# Microcontroller.net
KiCad netlist of a schematic drawn in Altium Designer
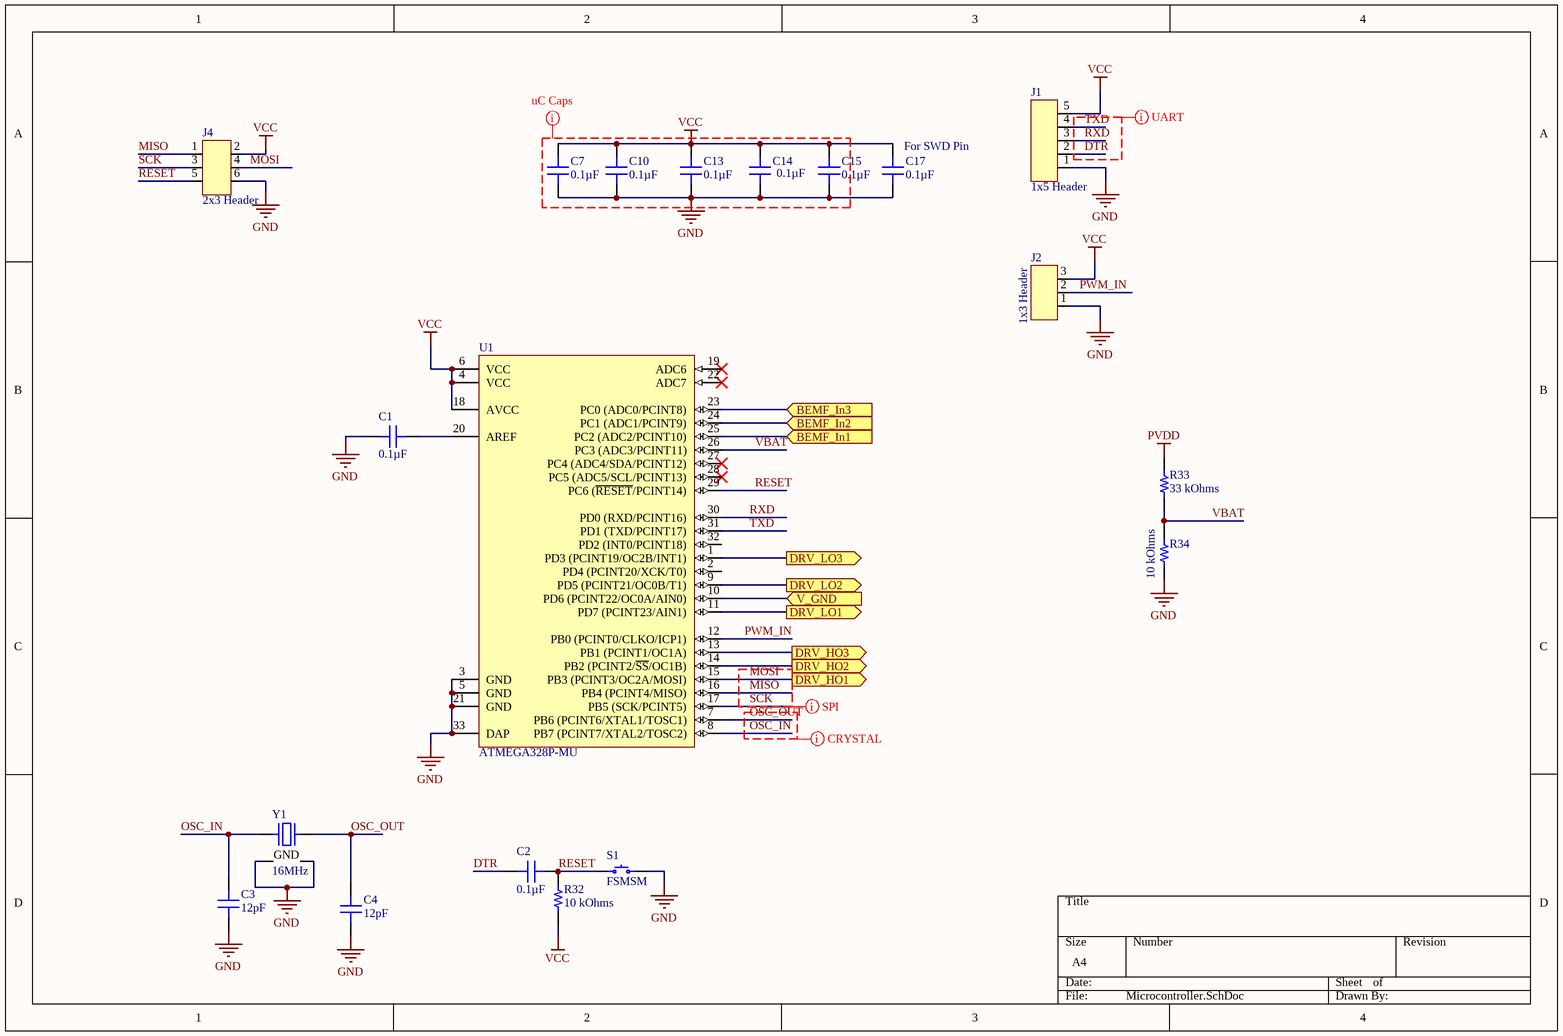
[diagram p0: Microcontroller.SchDoc]

(export (version "E")
  (design (tool "Eeschema 10.0.6"))
  (components
    (comp (ref "C1")
      (value "0.1µF")
      (footprint "CAP 0603_1608")
      (description "CAP CER 0.1UF 50V X7R 0603")
      (fields
        (field (name "PART NUMBER") "CML0603X7R104KT50V")
        (field (name "MANUFACTURER") "Stackpole Electronics Inc")
      )
      (libsource (lib "Celestial Altium Library - altium_library") (part "Capacitor"))
    )
    (comp (ref "C2")
      (value "0.1µF")
      (footprint "CAP 0603_1608")
      (description "CAP CER 0.1UF 50V X7R 0603")
      (fields
        (field (name "PART NUMBER") "CML0603X7R104KT50V")
        (field (name "MANUFACTURER") "Stackpole Electronics Inc")
      )
      (libsource (lib "Celestial Altium Library - altium_library") (part "Capacitor"))
    )
    (comp (ref "C3")
      (value "12pF")
      (footprint "CAP 0402_1005")
      (description "CAP CER 12PF 50V NP0 0402")
      (fields (field (name "PART NUMBER") "04025U120GAT2A") (field (name "MANUFACTURER") "AVX Corporation"))
      (libsource (lib "Celestial Altium Library - altium_library") (part "Capacitor"))
    )
    (comp (ref "C4")
      (value "12pF")
      (footprint "CAP 0402_1005")
      (description "CAP CER 12PF 50V NP0 0402")
      (fields (field (name "PART NUMBER") "04025U120GAT2A") (field (name "MANUFACTURER") "AVX Corporation"))
      (libsource (lib "Celestial Altium Library - altium_library") (part "Capacitor"))
    )
    (comp (ref "C7")
      (value "0.1µF")
      (footprint "CAP 0603_1608")
      (description "CAP CER 0.1UF 50V X7R 0603")
      (fields
        (field (name "PART NUMBER") "CML0603X7R104KT50V")
        (field (name "MANUFACTURER") "Stackpole Electronics Inc")
      )
      (libsource (lib "Celestial Altium Library - altium_library") (part "Capacitor"))
    )
    (comp (ref "C10")
      (value "0.1µF")
      (footprint "CAP 0603_1608")
      (description "CAP CER 0.1UF 50V X7R 0603")
      (fields
        (field (name "PART NUMBER") "CML0603X7R104KT50V")
        (field (name "MANUFACTURER") "Stackpole Electronics Inc")
      )
      (libsource (lib "Celestial Altium Library - altium_library") (part "Capacitor"))
    )
    (comp (ref "C13")
      (value "0.1µF")
      (footprint "CAP 0603_1608")
      (description "CAP CER 0.1UF 50V X7R 0603")
      (fields
        (field (name "PART NUMBER") "CML0603X7R104KT50V")
        (field (name "MANUFACTURER") "Stackpole Electronics Inc")
      )
      (libsource (lib "Celestial Altium Library - altium_library") (part "Capacitor"))
    )
    (comp (ref "C14")
      (value "0.1µF")
      (footprint "CAP 0603_1608")
      (description "CAP CER 0.1UF 50V X7R 0603")
      (fields
        (field (name "PART NUMBER") "CML0603X7R104KT50V")
        (field (name "MANUFACTURER") "Stackpole Electronics Inc")
      )
      (libsource (lib "Celestial Altium Library - altium_library") (part "Capacitor"))
    )
    (comp (ref "C15")
      (value "0.1µF")
      (footprint "CAP 0603_1608")
      (description "CAP CER 0.1UF 50V X7R 0603")
      (fields
        (field (name "PART NUMBER") "CML0603X7R104KT50V")
        (field (name "MANUFACTURER") "Stackpole Electronics Inc")
      )
      (libsource (lib "Celestial Altium Library - altium_library") (part "Capacitor"))
    )
    (comp (ref "C17")
      (value "0.1µF")
      (footprint "CAP 0603_1608")
      (description "CAP CER 0.1UF 50V X7R 0603")
      (fields
        (field (name "PART NUMBER") "CML0603X7R104KT50V")
        (field (name "MANUFACTURER") "Stackpole Electronics Inc")
      )
      (libsource (lib "Celestial Altium Library - altium_library") (part "Capacitor"))
    )
    (comp (ref "J1")
      (value "1x5 Header")
      (footprint "1X5-HEADER")
      (description "1X5 Male Header 2.54mm")
      (libsource (lib "UserIntegrated") (part "1x5 Header"))
    )
    (comp (ref "J2")
      (value "1x3 Header")
      (footprint "1x3Header")
      (description "1x3 Male Header 2.54mm")
      (libsource (lib "UserIntegrated") (part "1x3 Header"))
    )
    (comp (ref "J4")
      (value "2x3 Header")
      (footprint "3x2 Header")
      (description "2x3 Male Header 2.54mm")
      (libsource (lib "UserIntegrated") (part "2x3 Header"))
    )
    (comp (ref "R32")
      (value "10 kOhms")
      (footprint "RES 0805_2012")
      (description "RESTHINFILM 0805 10K0 0.1% 125MW")
      (fields (field (name "PART NUMBER") "CRT0805-BY-1002EST") (field (name "MANUFACTURER") "Bourns Inc."))
      (libsource (lib "Celestial Altium Library - altium_library") (part "Resistor"))
    )
    (comp (ref "R33")
      (value "33 kOhms")
      (footprint "RES 0805_2012")
      (description "RES SMD 33K OHM 1% 1/8W 0805")
      (fields (field (name "PART NUMBER") "CR0805-FX-3302ELF") (field (name "MANUFACTURER") "Bourns Inc."))
      (libsource (lib "Celestial Altium Library - altium_library") (part "Resistor"))
    )
    (comp (ref "R34")
      (value "10 kOhms")
      (footprint "RES 0805_2012")
      (description "RES 10K OHM 1% 1/8W 0805")
      (fields
        (field (name "PART NUMBER") "RN73R2ATTD1002F25")
        (field (name "MANUFACTURER") "KOA Speer Electronics, Inc.")
      )
      (libsource (lib "Celestial Altium Library - altium_library") (part "Resistor"))
    )
    (comp (ref "S1")
      (value "FSMSM")
      (footprint "TE FSMSMTR")
      (description "SWITCH TACTILE SPST-NO 0.05A 24V")
      (fields (field (name "MANUFACTURER") "TE Connectivity ALCOSWITCH Switches"))
      (libsource (lib "Celestial Altium Library - altium_library") (part "SPST-NO 2 PIN"))
    )
    (comp (ref "U1")
      (value "ATMEGA328P-MU")
      (footprint "QFN50P500X500X100_HS-33N")
      (libsource (lib "UserIntegrated") (part "ATMEGA328P-MU"))
    )
    (comp (ref "Y1")
      (value "16MHz")
      (footprint "NDK NX2520SA")
      (description "CRYSTAL 16MHZ 8PF SMD")
      (fields
        (field (name "PART NUMBER") "NX2520SA-16MHZ-EXS00A-CS11340")
        (field (name "MANUFACTURER") "NDK America, Inc.")
      )
      (libsource (lib "Celestial Altium Library - altium_library") (part "NDK Crystal NX2520SA"))
    )
  )
  (nets
    (net (code "1") (name "/BEMF_In1") (class "Default")
      (node (ref "U1") (pin "25") (pinfunction "PC2_(ADC2/PCINT10)_25") (pintype "bidirectional"))
    )
    (net (code "2") (name "/BEMF_In2") (class "Default")
      (node (ref "U1") (pin "24") (pinfunction "PC1_(ADC1/PCINT9)_24") (pintype "bidirectional"))
    )
    (net (code "3") (name "/BEMF_In3") (class "Default")
      (node (ref "U1") (pin "23") (pinfunction "PC0_(ADC0/PCINT8)_23") (pintype "bidirectional"))
    )
    (net (code "4") (name "/DRV_HO2") (class "Default")
      (node (ref "U1") (pin "14") (pinfunction "PB2_(PCINT2/~{SS}/OC1B)_14") (pintype "bidirectional"))
    )
    (net (code "5") (name "/DRV_HO3") (class "Default")
      (node (ref "U1") (pin "13") (pinfunction "PB1_(PCINT1/OC1A)_13") (pintype "bidirectional"))
    )
    (net (code "6") (name "/DRV_LO1") (class "Default")
      (node (ref "U1") (pin "11") (pinfunction "PD7_(PCINT23/AIN1)_11") (pintype "bidirectional"))
    )
    (net (code "7") (name "/DRV_LO2") (class "Default")
      (node (ref "U1") (pin "9") (pinfunction "PD5_(PCINT21/OC0B/T1)_9") (pintype "bidirectional"))
    )
    (net (code "8") (name "/DRV_LO3") (class "Default")
      (node (ref "U1") (pin "1") (pinfunction "PD3_(PCINT19/OC2B/INT1)_1") (pintype "bidirectional"))
    )
    (net (code "9") (name "/DTR") (class "Default")
      (node (ref "C2") (pin "2") (pinfunction "2_2") (pintype "passive"))
      (node (ref "J1") (pin "2") (pintype "passive"))
    )
    (net (code "10") (name "/MISO") (class "Default")
      (node (ref "J4") (pin "1") (pintype "passive"))
      (node (ref "U1") (pin "16") (pinfunction "PB4_(PCINT4/MISO)_16") (pintype "bidirectional"))
    )
    (net (code "11") (name "/MOSI") (class "Default")
      (node (ref "J4") (pin "4") (pintype "passive"))
      (node (ref "U1") (pin "15") (pinfunction "PB3_(PCINT3/OC2A/MOSI)_15") (pintype "bidirectional"))
    )
    (net (code "12") (name "/OSC_IN") (class "Default")
      (node (ref "C3") (pin "2") (pinfunction "2_2") (pintype "passive"))
      (node (ref "U1") (pin "8") (pinfunction "PB7_(PCINT7/XTAL2/TOSC2)_8") (pintype "bidirectional"))
      (node (ref "Y1") (pin "1") (pinfunction "1_1") (pintype "passive"))
    )
    (net (code "13") (name "/OSC_OUT") (class "Default")
      (node (ref "C4") (pin "2") (pinfunction "2_2") (pintype "passive"))
      (node (ref "U1") (pin "7") (pinfunction "PB6_(PCINT6/XTAL1/TOSC1)_7") (pintype "bidirectional"))
      (node (ref "Y1") (pin "3") (pinfunction "3_3") (pintype "passive"))
    )
    (net (code "14") (name "/PWM_IN") (class "Default")
      (node (ref "J2") (pin "2") (pintype "passive"))
      (node (ref "U1") (pin "12") (pinfunction "PB0_(PCINT0/CLKO/ICP1)_12") (pintype "bidirectional"))
    )
    (net (code "15") (name "/RESET") (class "Default")
      (node (ref "C2") (pin "1") (pinfunction "1_1") (pintype "passive"))
      (node (ref "J4") (pin "5") (pintype "passive"))
      (node (ref "R32") (pin "1") (pinfunction "1_1") (pintype "passive"))
      (node (ref "S1") (pin "1") (pinfunction "1_1") (pintype "passive"))
      (node (ref "U1") (pin "29") (pinfunction "PC6_(~{RESET}/PCINT14)_29") (pintype "bidirectional"))
    )
    (net (code "16") (name "/RXD") (class "Default")
      (node (ref "J1") (pin "3") (pintype "passive"))
      (node (ref "U1") (pin "30") (pinfunction "PD0_(RXD/PCINT16)_30") (pintype "bidirectional"))
    )
    (net (code "17") (name "/SCK") (class "Default")
      (node (ref "J4") (pin "3") (pintype "passive"))
      (node (ref "U1") (pin "17") (pinfunction "PB5_(SCK/PCINT5)_17") (pintype "bidirectional"))
    )
    (net (code "18") (name "/TXD") (class "Default")
      (node (ref "J1") (pin "4") (pintype "passive"))
      (node (ref "U1") (pin "31") (pinfunction "PD1_(TXD/PCINT17)_31") (pintype "bidirectional"))
    )
    (net (code "19") (name "/VBAT") (class "Default")
      (node (ref "R33") (pin "1") (pinfunction "1_1") (pintype "passive"))
      (node (ref "R34") (pin "2") (pinfunction "2_2") (pintype "passive"))
      (node (ref "U1") (pin "26") (pinfunction "PC3_(ADC3/PCINT11)_26") (pintype "bidirectional"))
    )
    (net (code "20") (name "/V_GND") (class "Default")
      (node (ref "U1") (pin "10") (pinfunction "PD6_(PCINT22/OC0A/AIN0)_10") (pintype "bidirectional"))
    )
    (net (code "21") (name "GND") (class "Default")
      (node (ref "C1") (pin "2") (pinfunction "2_2") (pintype "passive"))
      (node (ref "C10") (pin "1") (pinfunction "1_1") (pintype "passive"))
      (node (ref "C13") (pin "1") (pinfunction "1_1") (pintype "passive"))
      (node (ref "C14") (pin "1") (pinfunction "1_1") (pintype "passive"))
      (node (ref "C15") (pin "1") (pinfunction "1_1") (pintype "passive"))
      (node (ref "C17") (pin "2") (pinfunction "2_2") (pintype "passive"))
      (node (ref "C3") (pin "1") (pinfunction "1_1") (pintype "passive"))
      (node (ref "C4") (pin "1") (pinfunction "1_1") (pintype "passive"))
      (node (ref "C7") (pin "1") (pinfunction "1_1") (pintype "passive"))
      (node (ref "J1") (pin "1") (pintype "passive"))
      (node (ref "J2") (pin "1") (pintype "passive"))
      (node (ref "J4") (pin "6") (pintype "passive"))
      (node (ref "R34") (pin "1") (pinfunction "1_1") (pintype "passive"))
      (node (ref "S1") (pin "2") (pinfunction "2_2") (pintype "passive"))
      (node (ref "U1") (pin "21") (pinfunction "GND_21") (pintype "power_in"))
      (node (ref "U1") (pin "3") (pinfunction "GND_3") (pintype "power_in"))
      (node (ref "U1") (pin "33") (pinfunction "DAP_33") (pintype "power_in"))
      (node (ref "U1") (pin "5") (pinfunction "GND_5") (pintype "power_in"))
      (node (ref "Y1") (pin "2") (pinfunction "GND_2") (pintype "passive"))
      (node (ref "Y1") (pin "4") (pinfunction "GND_4") (pintype "passive"))
    )
    (net (code "22") (name "Net-(U1-AREF)") (class "Default")
      (node (ref "C1") (pin "1") (pinfunction "1_1") (pintype "passive"))
      (node (ref "U1") (pin "20") (pinfunction "AREF_20") (pintype "passive"))
    )
    (net (code "23") (name "PVDD") (class "Default")
      (node (ref "R33") (pin "2") (pinfunction "2_2") (pintype "passive"))
    )
    (net (code "24") (name "VCC") (class "Default")
      (node (ref "C10") (pin "2") (pinfunction "2_2") (pintype "passive"))
      (node (ref "C13") (pin "2") (pinfunction "2_2") (pintype "passive"))
      (node (ref "C14") (pin "2") (pinfunction "2_2") (pintype "passive"))
      (node (ref "C15") (pin "2") (pinfunction "2_2") (pintype "passive"))
      (node (ref "C17") (pin "1") (pinfunction "1_1") (pintype "passive"))
      (node (ref "C7") (pin "2") (pinfunction "2_2") (pintype "passive"))
      (node (ref "J1") (pin "5") (pintype "passive"))
      (node (ref "J2") (pin "3") (pintype "passive"))
      (node (ref "J4") (pin "2") (pintype "passive"))
      (node (ref "R32") (pin "2") (pinfunction "2_2") (pintype "passive"))
      (node (ref "U1") (pin "18") (pinfunction "AVCC_18") (pintype "power_in"))
      (node (ref "U1") (pin "4") (pinfunction "VCC_4") (pintype "power_in"))
      (node (ref "U1") (pin "6") (pinfunction "VCC_6") (pintype "power_in"))
    )
    (net (code "25") (name "unconnected-(U1-ADC6-Pad19)") (class "Default")
      (node (ref "U1") (pin "19") (pinfunction "ADC6_19") (pintype "input+no_connect"))
    )
    (net (code "26") (name "unconnected-(U1-ADC7-Pad22)") (class "Default")
      (node (ref "U1") (pin "22") (pinfunction "ADC7_22") (pintype "input+no_connect"))
    )
    (net (code "27") (name "unconnected-(U1-PC4_(ADC4{slash}SDA{slash}PCINT12)-Pad27)") (class "Default")
      (node (ref "U1") (pin "27") (pinfunction "PC4_(ADC4/SDA/PCINT12)_27") (pintype "bidirectional+no_connect"))
    )
    (net (code "28") (name "unconnected-(U1-PC5_(ADC5{slash}SCL{slash}PCINT13)-Pad28)") (class "Default")
      (node (ref "U1") (pin "28") (pinfunction "PC5_(ADC5/SCL/PCINT13)_28") (pintype "bidirectional+no_connect"))
    )
    (net (code "29") (name "unconnected-(U1-PD2_(INT0{slash}PCINT18)-Pad32)") (class "Default")
      (node (ref "U1") (pin "32") (pinfunction "PD2_(INT0/PCINT18)_32") (pintype "bidirectional"))
    )
    (net (code "30") (name "unconnected-(U1-PD4_(PCINT20{slash}XCK{slash}T0)-Pad2)") (class "Default")
      (node (ref "U1") (pin "2") (pinfunction "PD4_(PCINT20/XCK/T0)_2") (pintype "bidirectional"))
    )
  )
)
